# nufsr-power-decoupling.net
KiCad netlist of a schematic drawn in Altium Designer
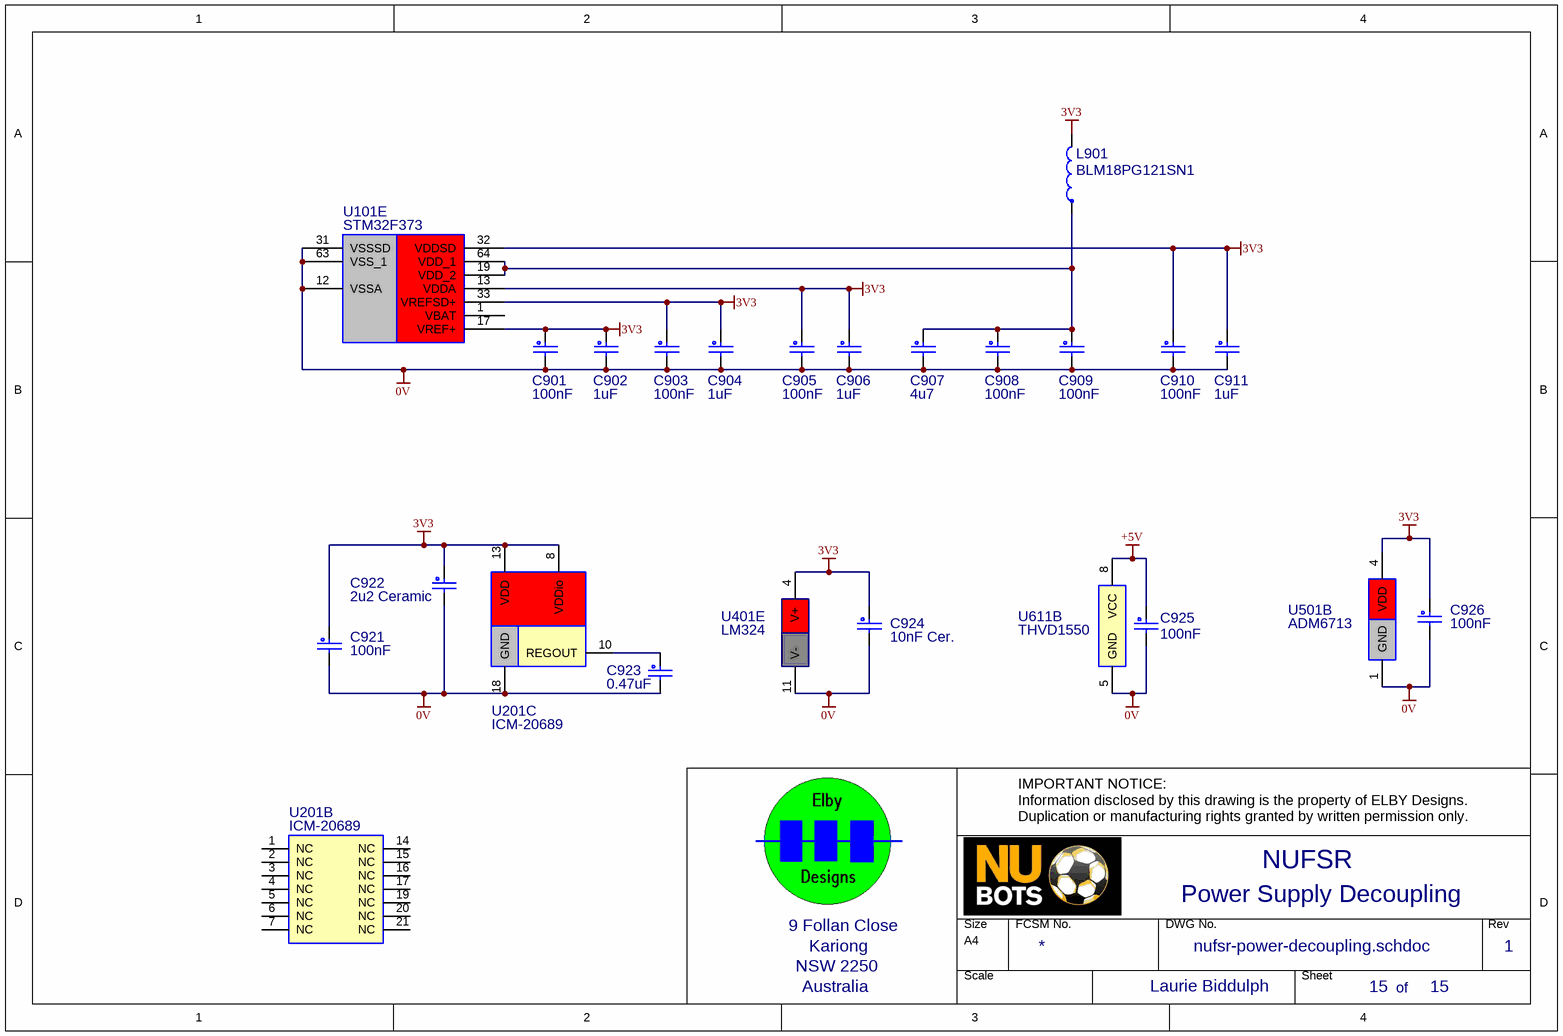
[diagram p0: nufsr-power-decoupling.schdoc]

(export (version "E")
  (design (tool "Eeschema 10.0.6"))
  (components
    (comp (ref "C901")
      (value "100nF")
      (footprint "0603(LB)")
      (description "Monolithic Ceramic")
      (libsource (lib "capacitor") (part "CC-100NF(LB)"))
    )
    (comp (ref "C902")
      (value "1uF")
      (footprint "0805(LB)")
      (description "1uF Ceramic")
      (libsource (lib "capacitor") (part "CC-1000NF(LB)"))
    )
    (comp (ref "C903")
      (value "100nF")
      (footprint "0603(LB)")
      (description "Monolithic Ceramic")
      (libsource (lib "capacitor") (part "CC-100NF(LB)"))
    )
    (comp (ref "C904")
      (value "1uF")
      (footprint "0805(LB)")
      (description "1uF Ceramic")
      (libsource (lib "capacitor") (part "CC-1000NF(LB)"))
    )
    (comp (ref "C905")
      (value "100nF")
      (footprint "0603(LB)")
      (description "Monolithic Ceramic")
      (libsource (lib "capacitor") (part "CC-100NF(LB)"))
    )
    (comp (ref "C906")
      (value "1uF")
      (footprint "0805(LB)")
      (description "1uF Ceramic")
      (libsource (lib "capacitor") (part "CC-1000NF(LB)"))
    )
    (comp (ref "C907")
      (value "4u7")
      (footprint "0805(LB)")
      (description "4.7uF Ceramic")
      (libsource (lib "capacitor") (part "CC-4700NF(LB)"))
    )
    (comp (ref "C908")
      (value "100nF")
      (footprint "0603(LB)")
      (description "Monolithic Ceramic")
      (libsource (lib "capacitor") (part "CC-100NF(LB)"))
    )
    (comp (ref "C909")
      (value "100nF")
      (footprint "0603(LB)")
      (description "Monolithic Ceramic")
      (libsource (lib "capacitor") (part "CC-100NF(LB)"))
    )
    (comp (ref "C910")
      (value "100nF")
      (footprint "0603(LB)")
      (description "Monolithic Ceramic")
      (libsource (lib "capacitor") (part "CC-100NF(LB)"))
    )
    (comp (ref "C911")
      (value "1uF")
      (footprint "0805(LB)")
      (description "1uF Ceramic")
      (libsource (lib "capacitor") (part "CC-1000NF(LB)"))
    )
    (comp (ref "C921")
      (value "100nF")
      (footprint "0603(LB)")
      (description "Monolithic Ceramic")
      (libsource (lib "capacitor") (part "CC-100NF(LB)"))
    )
    (comp (ref "C922")
      (value "2u2 Ceramic")
      (footprint "0805(LB)")
      (description "2.2uF Ceramic")
      (libsource (lib "capacitor") (part "CC-2200NF(LB)"))
    )
    (comp (ref "C923")
      (value "0.47uF")
      (footprint "0805(LB)")
      (description "63V 10% Metallised Polyester")
      (libsource (lib "capacitor") (part "CP-470NF(LB)"))
    )
    (comp (ref "C924")
      (value "10nF Cer.")
      (footprint "0603(LB)")
      (description "Monolithic Ceramic")
      (libsource (lib "capacitor") (part "CC-10NF(LB)"))
    )
    (comp (ref "C925")
      (value "100nF")
      (footprint "0603(LB)")
      (description "Monolithic Ceramic")
      (libsource (lib "capacitor") (part "CC-100NF(LB)"))
    )
    (comp (ref "C926")
      (value "100nF")
      (footprint "0603(LB)")
      (description "Monolithic Ceramic")
      (libsource (lib "capacitor") (part "CC-100NF(LB)"))
    )
    (comp (ref "L901")
      (value "BLM18PG121SN1")
      (footprint "0603(LB)")
      (description "Ferrite Bead")
      (libsource (lib "passive") (part "FERRITE-BEAD(LB)"))
    )
    (comp (ref "U101")
      (value "STM32F373")
      (footprint "LQFP-64_10x10(LB)")
      (description "32-bit Microcontroller")
      (fields
        (field (name "MANUFACTURER_PART_NUMBER") "stm32f74xzxt")
        (field (name "COPYRIGHT") "Copyright (C) 2016 Accelerated Designs. All rights reserved")
      )
      (libsource (lib "NuSense") (part "STM32F373"))
    )
    (comp (ref "U201")
      (value "ICM-20689")
      (footprint "QFN-24")
      (description "Motion Tracking")
      (libsource (lib "NuBots") (part "ICM-20869"))
    )
    (comp (ref "U401")
      (value "LM324")
      (description "Quad Low-noise JFET Op-amp")
      (libsource (lib "ic") (part "LM324(LB)"))
    )
    (comp (ref "U501")
      (value "ADM6713")
      (footprint "SC70-4")
      (description "Microprocessor Supervisory Circuit")
      (libsource (lib "NuBots") (part "ADM6713"))
    )
    (comp (ref "U611")
      (value "THVD1550")
      (footprint "SO-8(LB)")
      (description "RS485 Transceiver 18kV 50mbps")
      (libsource (lib "NuBots") (part "THVD1550(LB)"))
    )
  )
  (nets
    (net (code "1") (name "+5V") (class "Default")
      (node (ref "C925") (pin "1") (pintype "passive"))
      (node (ref "U611") (pin "8") (pinfunction "VCC_8") (pintype "power_in"))
    )
    (net (code "2") (name "0V") (class "Default")
      (node (ref "C901") (pin "2") (pintype "passive"))
      (node (ref "C902") (pin "2") (pintype "passive"))
      (node (ref "C903") (pin "2") (pintype "passive"))
      (node (ref "C904") (pin "2") (pintype "passive"))
      (node (ref "C905") (pin "2") (pintype "passive"))
      (node (ref "C906") (pin "2") (pintype "passive"))
      (node (ref "C907") (pin "2") (pintype "passive"))
      (node (ref "C908") (pin "2") (pintype "passive"))
      (node (ref "C909") (pin "2") (pintype "passive"))
      (node (ref "C910") (pin "2") (pintype "passive"))
      (node (ref "C911") (pin "2") (pintype "passive"))
      (node (ref "C921") (pin "2") (pintype "passive"))
      (node (ref "C922") (pin "2") (pintype "passive"))
      (node (ref "C923") (pin "2") (pintype "passive"))
      (node (ref "C924") (pin "2") (pintype "passive"))
      (node (ref "C925") (pin "2") (pintype "passive"))
      (node (ref "C926") (pin "2") (pintype "passive"))
      (node (ref "U101") (pin "12") (pinfunction "VSSA_12") (pintype "power_in"))
      (node (ref "U101") (pin "31") (pinfunction "VSSSD_31") (pintype "power_in"))
      (node (ref "U101") (pin "63") (pinfunction "VSS_1_63") (pintype "power_in"))
      (node (ref "U201") (pin "18") (pinfunction "GND_18") (pintype "power_in"))
      (node (ref "U401") (pin "11") (pinfunction "V-_11") (pintype "power_in"))
      (node (ref "U501") (pin "1") (pinfunction "GND_1") (pintype "power_in"))
      (node (ref "U611") (pin "5") (pinfunction "GND_5") (pintype "power_in"))
    )
    (net (code "3") (name "3V3") (class "Default")
      (node (ref "C901") (pin "1") (pintype "passive"))
      (node (ref "C902") (pin "1") (pintype "passive"))
      (node (ref "C903") (pin "1") (pintype "passive"))
      (node (ref "C904") (pin "1") (pintype "passive"))
      (node (ref "C905") (pin "1") (pintype "passive"))
      (node (ref "C906") (pin "1") (pintype "passive"))
      (node (ref "C910") (pin "1") (pintype "passive"))
      (node (ref "C911") (pin "1") (pintype "passive"))
      (node (ref "C921") (pin "1") (pintype "passive"))
      (node (ref "C922") (pin "1") (pintype "passive"))
      (node (ref "C924") (pin "1") (pintype "passive"))
      (node (ref "C926") (pin "1") (pintype "passive"))
      (node (ref "L901") (pin "2") (pinfunction "2_2") (pintype "passive"))
      (node (ref "U101") (pin "13") (pinfunction "VDDA_13") (pintype "power_in"))
      (node (ref "U101") (pin "17") (pinfunction "VREF+_17") (pintype "power_in"))
      (node (ref "U101") (pin "32") (pinfunction "VDDSD_32") (pintype "power_in"))
      (node (ref "U101") (pin "33") (pinfunction "VREFSD+_33") (pintype "power_in"))
      (node (ref "U201") (pin "13") (pinfunction "VDD_13") (pintype "power_in"))
      (node (ref "U201") (pin "8") (pinfunction "VDDio_8") (pintype "power_in"))
      (node (ref "U401") (pin "4") (pinfunction "V+_4") (pintype "power_in"))
      (node (ref "U501") (pin "4") (pinfunction "VDD_4") (pintype "power_in"))
    )
    (net (code "4") (name "Net-(U101E-VDD_1)") (class "Default")
      (node (ref "C907") (pin "1") (pintype "passive"))
      (node (ref "C908") (pin "1") (pintype "passive"))
      (node (ref "C909") (pin "1") (pintype "passive"))
      (node (ref "L901") (pin "1") (pinfunction "1_1") (pintype "passive"))
      (node (ref "U101") (pin "19") (pinfunction "VDD_2_19") (pintype "power_in"))
      (node (ref "U101") (pin "64") (pinfunction "VDD_1_64") (pintype "power_in"))
    )
    (net (code "5") (name "Net-(U201C-REGOUT)") (class "Default")
      (node (ref "C923") (pin "1") (pintype "passive"))
      (node (ref "U201") (pin "10") (pinfunction "REGOUT_10") (pintype "passive"))
    )
    (net (code "6") (name "unconnected-(U101E-VBAT-Pad1)") (class "Default")
      (node (ref "U101") (pin "1") (pinfunction "VBAT_1") (pintype "power_in"))
    )
    (net (code "7") (name "unconnected-(U201B-NC-Pad1)") (class "Default")
      (node (ref "U201") (pin "1") (pinfunction "NC_1") (pintype "passive"))
    )
    (net (code "8") (name "unconnected-(U201B-NC-Pad2)") (class "Default")
      (node (ref "U201") (pin "2") (pinfunction "NC_2") (pintype "passive"))
    )
    (net (code "9") (name "unconnected-(U201B-NC-Pad3)") (class "Default")
      (node (ref "U201") (pin "3") (pinfunction "NC_3") (pintype "passive"))
    )
    (net (code "10") (name "unconnected-(U201B-NC-Pad4)") (class "Default")
      (node (ref "U201") (pin "4") (pinfunction "NC_4") (pintype "passive"))
    )
    (net (code "11") (name "unconnected-(U201B-NC-Pad5)") (class "Default")
      (node (ref "U201") (pin "5") (pinfunction "NC_5") (pintype "passive"))
    )
    (net (code "12") (name "unconnected-(U201B-NC-Pad6)") (class "Default")
      (node (ref "U201") (pin "6") (pinfunction "NC_6") (pintype "passive"))
    )
    (net (code "13") (name "unconnected-(U201B-NC-Pad7)") (class "Default")
      (node (ref "U201") (pin "7") (pinfunction "NC_7") (pintype "passive"))
    )
    (net (code "14") (name "unconnected-(U201B-NC-Pad14)") (class "Default")
      (node (ref "U201") (pin "14") (pinfunction "NC_14") (pintype "passive"))
    )
    (net (code "15") (name "unconnected-(U201B-NC-Pad15)") (class "Default")
      (node (ref "U201") (pin "15") (pinfunction "NC_15") (pintype "passive"))
    )
    (net (code "16") (name "unconnected-(U201B-NC-Pad16)") (class "Default")
      (node (ref "U201") (pin "16") (pinfunction "NC_16") (pintype "passive"))
    )
    (net (code "17") (name "unconnected-(U201B-NC-Pad17)") (class "Default")
      (node (ref "U201") (pin "17") (pinfunction "NC_17") (pintype "passive"))
    )
    (net (code "18") (name "unconnected-(U201B-NC-Pad19)") (class "Default")
      (node (ref "U201") (pin "19") (pinfunction "NC_19") (pintype "passive"))
    )
    (net (code "19") (name "unconnected-(U201B-NC-Pad20)") (class "Default")
      (node (ref "U201") (pin "20") (pinfunction "NC_20") (pintype "passive"))
    )
    (net (code "20") (name "unconnected-(U201B-NC-Pad21)") (class "Default")
      (node (ref "U201") (pin "21") (pinfunction "NC_21") (pintype "passive"))
    )
  )
)
